# zulu_a7_3.net
KiCad netlist of a schematic drawn in Altium Designer
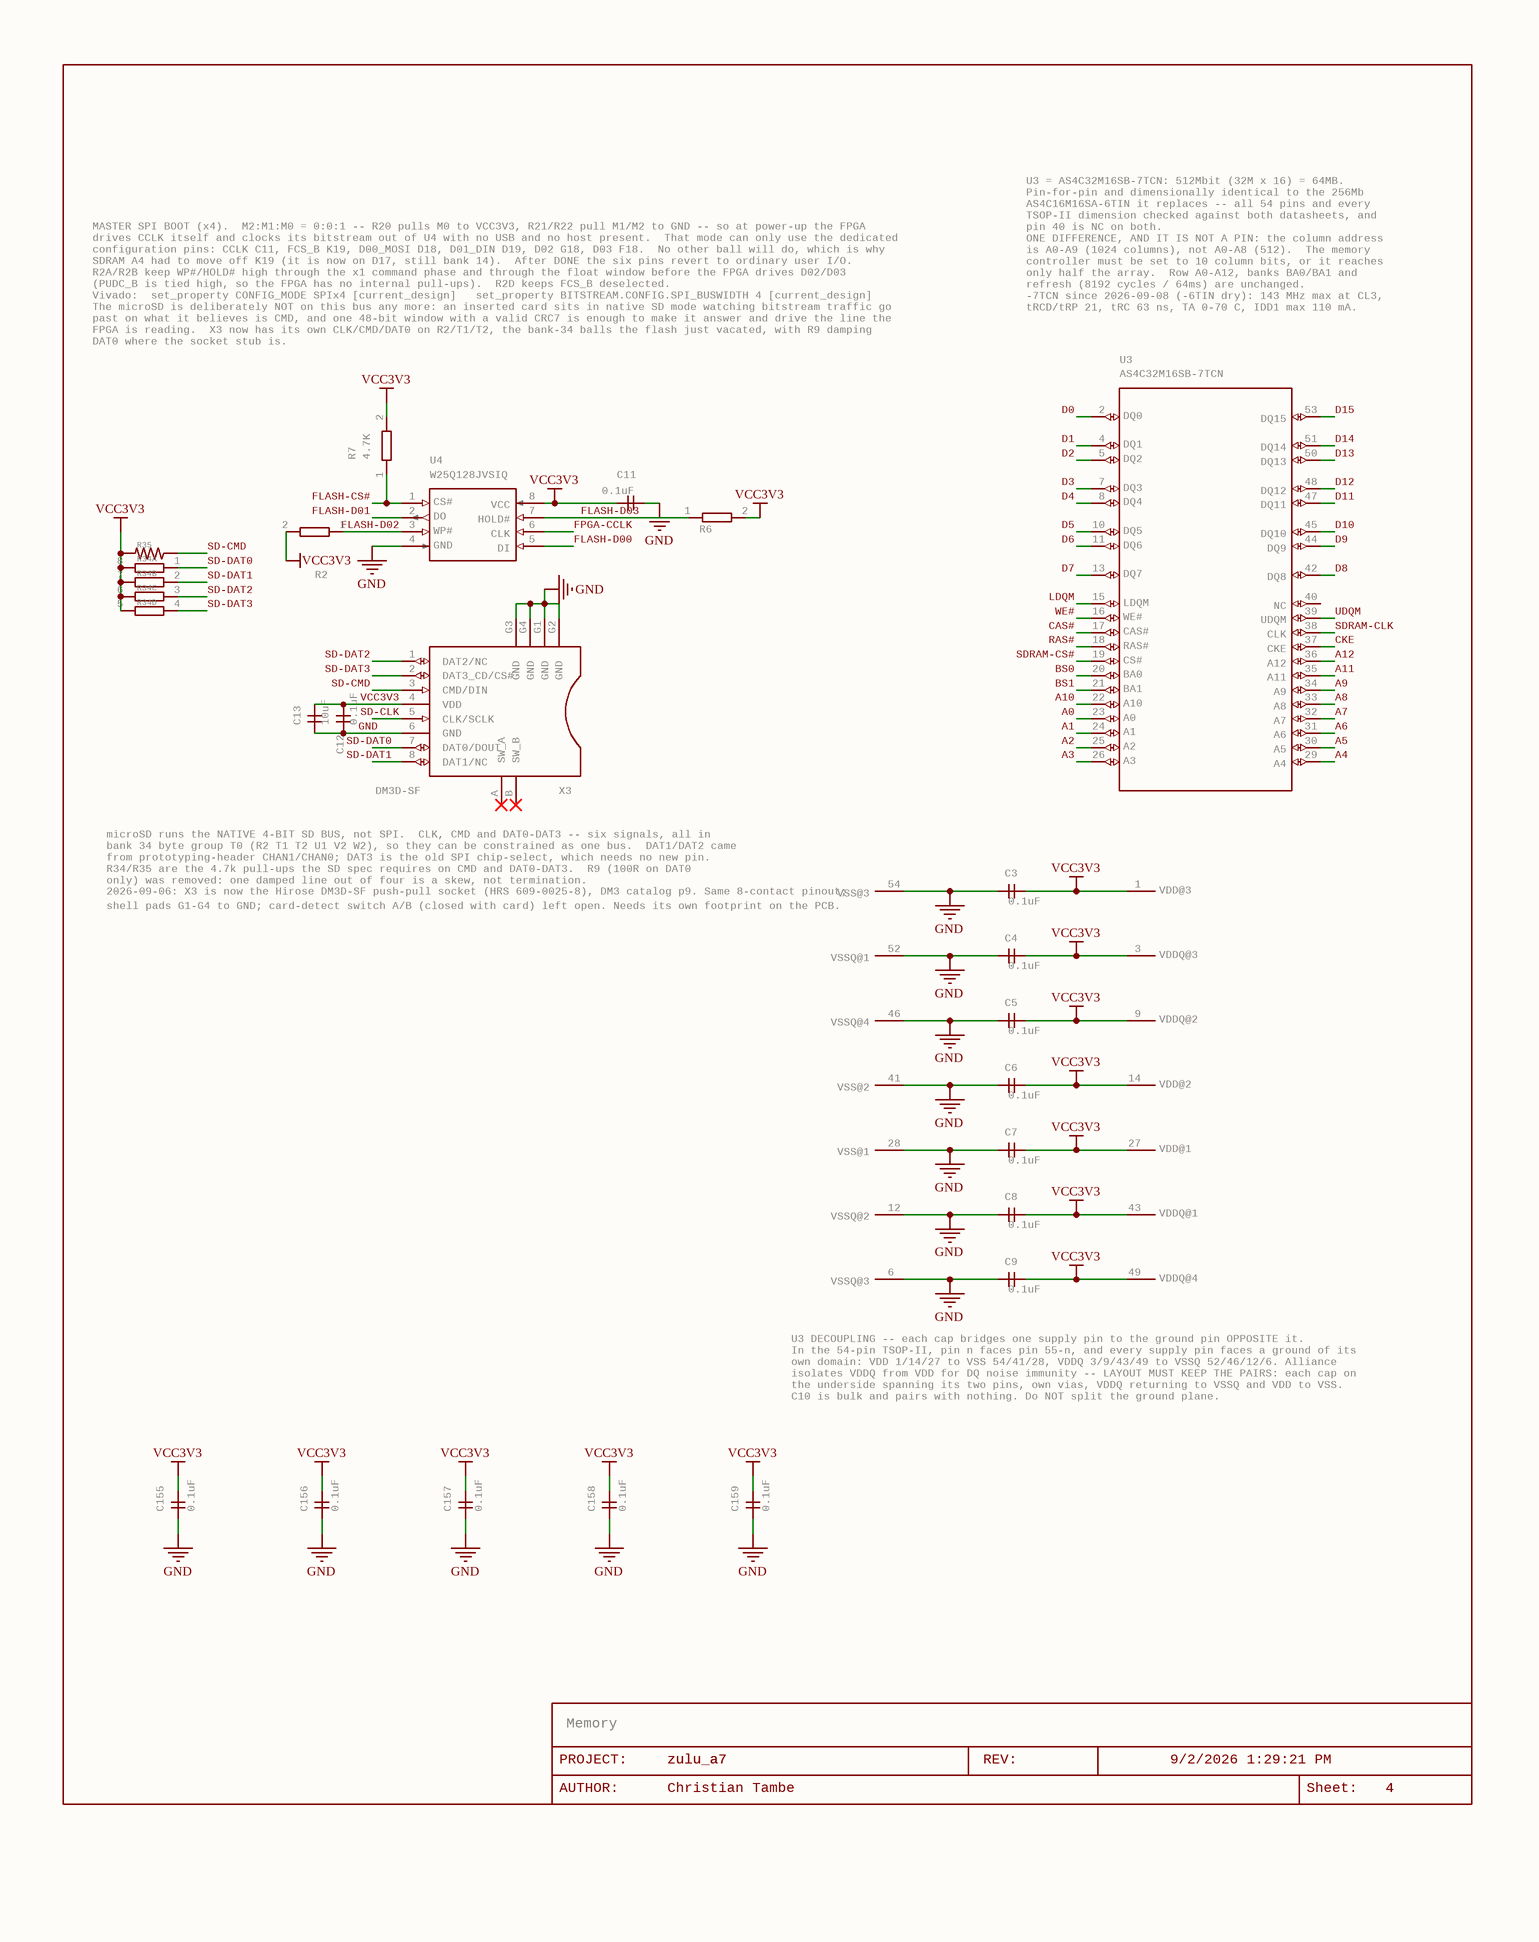
[diagram p0: zulu_a7_3.SchDoc]

(export (version "E")
  (design (tool "Eeschema 10.0.6"))
  (components
    (comp (ref "C3")
      (value "0.1uF")
      (footprint "C0402")
      (description "CAPACITOR, generic non-polarized, horizontal pins")
      (fields (field (name "MANF") "Murata"))
      (libsource (lib "") (part "C-GENERICC0402_3"))
    )
    (comp (ref "C4")
      (value "0.1uF")
      (footprint "C0402")
      (description "CAPACITOR, generic non-polarized, horizontal pins")
      (fields (field (name "MANF") "Murata"))
      (libsource (lib "") (part "C-GENERICC0402_6"))
    )
    (comp (ref "C5")
      (value "0.1uF")
      (footprint "C0402")
      (description "CAPACITOR, generic non-polarized, horizontal pins")
      (fields (field (name "MANF") "Murata"))
      (libsource (lib "") (part "C-GENERICC0402_5"))
    )
    (comp (ref "C6")
      (value "0.1uF")
      (footprint "C0402")
      (description "CAPACITOR, generic non-polarized, horizontal pins")
      (fields (field (name "MANF") "Murata"))
      (libsource (lib "rcl") (part "C-GENERICC0402"))
    )
    (comp (ref "C7")
      (value "0.1uF")
      (footprint "C0402")
      (description "CAPACITOR, generic non-polarized, horizontal pins")
      (fields (field (name "MANF") "Murata"))
      (libsource (lib "") (part "C-GENERICC0402_2"))
    )
    (comp (ref "C8")
      (value "0.1uF")
      (footprint "C0402")
      (description "CAPACITOR, generic non-polarized, horizontal pins")
      (fields (field (name "MANF") "Murata"))
      (libsource (lib "") (part "C-GENERICC0402_1"))
    )
    (comp (ref "C9")
      (value "0.1uF")
      (footprint "C0402")
      (description "CAPACITOR, generic non-polarized, horizontal pins")
      (fields (field (name "MANF") "Murata"))
      (libsource (lib "") (part "C-GENERICC0402_4"))
    )
    (comp (ref "C11")
      (value "0.1uF")
      (footprint "C0402")
      (description "CAPACITOR, generic non-polarized, horizontal pins")
      (fields (field (name "MANF") "Murata"))
      (libsource (lib "") (part "C-GENERICC0402_4"))
    )
    (comp (ref "C12")
      (value "0.1uF")
      (footprint "C0402")
      (description "CAPACITOR, generic non-polarized, horizontal pins")
      (fields (field (name "MANF") "Murata"))
      (libsource (lib "") (part "C-GENERICC0402_4"))
    )
    (comp (ref "C13")
      (value "10uF")
      (footprint "C0603")
      (description "CAPACITOR, generic non-polarized, horizontal pins")
      (fields (field (name "MANF") "Murata"))
      (libsource (lib "rcl") (part "C-GENERICC0603"))
    )
    (comp (ref "C155")
      (value "0.1uF")
      (footprint "C0201")
      (description "CAPACITOR, generic non-polarized, horizontal pins")
      (fields (field (name "MANF") "Murata"))
      (libsource (lib "rcl") (part "C-GENERICC0201"))
    )
    (comp (ref "C156")
      (value "0.1uF")
      (footprint "C0201")
      (description "CAPACITOR, generic non-polarized, horizontal pins")
      (fields (field (name "MANF") "Murata"))
      (libsource (lib "rcl") (part "C-GENERICC0201"))
    )
    (comp (ref "C157")
      (value "0.1uF")
      (footprint "C0201")
      (description "CAPACITOR, generic non-polarized, horizontal pins")
      (fields (field (name "MANF") "Murata"))
      (libsource (lib "rcl") (part "C-GENERICC0201"))
    )
    (comp (ref "C158")
      (value "0.1uF")
      (footprint "C0201")
      (description "CAPACITOR, generic non-polarized, horizontal pins")
      (fields (field (name "MANF") "Murata"))
      (libsource (lib "rcl") (part "C-GENERICC0201"))
    )
    (comp (ref "C159")
      (value "0.1uF")
      (footprint "C0201")
      (description "CAPACITOR, generic non-polarized, horizontal pins")
      (fields (field (name "MANF") "Murata"))
      (libsource (lib "rcl") (part "C-GENERICC0201"))
    )
    (comp (ref "FRAME7")
      (value "DOCFIELD")
      (description "DOCUMENT FIELD")
      (fields
        (field (name "LAST_DATE_TIME") "9/2/2026 1:29:21 PM")
        (field (name "SHEET") "Sheet:")
        (field (name "SHEET_1") "4")
        (field (name "REV") "REV:")
        (field (name "PROJECT") "PROJECT:")
        (field (name "DRAWING_NAME") "zulu_a7")
        (field (name "AUTHOR") "Christian Tambe")
        (field (name "DRAWING_NAME_1") "zulu_a7")
        (field (name "SHEET_2") "4")
        (field (name "LIBRARYNAME") "ctambe")
      )
      (libsource (lib "ctambe") (part "DOCFIELD"))
    )
    (comp (ref "R2")
      (value "4.7K")
      (footprint "R0201")
      (fields (field (name "MANF") "Yageo"))
      (libsource (lib "rcl") (part "R-WIDER0201"))
    )
    (comp (ref "R6")
      (value "4.7K")
      (footprint "R0201")
      (fields (field (name "MANF") "Yageo"))
      (libsource (lib "rcl") (part "R-WIDER0201"))
    )
    (comp (ref "R7")
      (value "4.7K")
      (footprint "R0201")
      (fields (field (name "MANF") "Yageo"))
      (libsource (lib "rcl") (part "R-WIDER0201"))
    )
    (comp (ref "R34")
      (value "4.7K")
      (footprint "742C083")
      (description "Resistor 4-pack   Package of four resistors.")
      (fields (field (name "MANF") "CTS") (field (name "LIBRARYNAME") "ctambe"))
      (libsource (lib "ctambe") (part "RES4742"))
    )
    (comp (ref "R35")
      (value "4.7K")
      (footprint "R0402")
      (description "RESISTOR, American symbol")
      (fields (field (name "MANF") "Yageo"))
      (libsource (lib "rcl") (part "R-US_R0402"))
    )
    (comp (ref "U3")
      (value "AS4C32M16SB-7TCN")
      (footprint "TSOPII-54")
      (fields
        (field (name "GATE") "VDD@2")
        (field (name "MANF") "Alliance Memory")
        (field (name "PART") "U3")
        (field (name "LIBRARYNAME") "ctambe")
      )
      (libsource (lib "ctambe") (part "SDRAM-X16-ALLIANCE-512M"))
    )
    (comp (ref "U4")
      (value "W25Q128JVSIQ")
      (footprint "SOIC-8_208MIL")
      (description "SPI Flash")
      (fields
        (field (name "GATE") "CS#")
        (field (name "MANF") "Winbond")
        (field (name "PART") "U4")
        (field (name "LIBRARYNAME") "ctambe")
      )
      (libsource (lib "ctambe") (part "SPI_FLASH-SOIC_150_208"))
    )
    (comp (ref "X3")
      (value "DM3D-SF")
      (footprint "DM3D-SF")
      (description "microSD socket, push-pull, Hirose DM3D-SF")
      (fields (field (name "MANF") "Hirose") (field (name "LIBRARYNAME") "ctambe"))
      (libsource (lib "ctambe") (part "MICROSD_CONDM3D-SF"))
    )
  )
  (nets
    (net (code "1") (name "/A0") (class "Default")
      (node (ref "U3") (pin "23") (pinfunction "P$1_23") (pintype "bidirectional"))
    )
    (net (code "2") (name "/A1") (class "Default")
      (node (ref "U3") (pin "24") (pinfunction "P$1_24") (pintype "bidirectional"))
    )
    (net (code "3") (name "/A2") (class "Default")
      (node (ref "U3") (pin "25") (pinfunction "P$1_25") (pintype "bidirectional"))
    )
    (net (code "4") (name "/A3") (class "Default")
      (node (ref "U3") (pin "26") (pinfunction "P$1_26") (pintype "bidirectional"))
    )
    (net (code "5") (name "/A4") (class "Default")
      (node (ref "U3") (pin "29") (pinfunction "P$1_29") (pintype "bidirectional"))
    )
    (net (code "6") (name "/A5") (class "Default")
      (node (ref "U3") (pin "30") (pinfunction "P$1_30") (pintype "bidirectional"))
    )
    (net (code "7") (name "/A6") (class "Default")
      (node (ref "U3") (pin "31") (pinfunction "P$1_31") (pintype "bidirectional"))
    )
    (net (code "8") (name "/A7") (class "Default")
      (node (ref "U3") (pin "32") (pinfunction "P$1_32") (pintype "bidirectional"))
    )
    (net (code "9") (name "/A8") (class "Default")
      (node (ref "U3") (pin "33") (pinfunction "P$1_33") (pintype "bidirectional"))
    )
    (net (code "10") (name "/A9") (class "Default")
      (node (ref "U3") (pin "34") (pinfunction "P$1_34") (pintype "bidirectional"))
    )
    (net (code "11") (name "/A10") (class "Default")
      (node (ref "U3") (pin "22") (pinfunction "P$1_22") (pintype "bidirectional"))
    )
    (net (code "12") (name "/A11") (class "Default")
      (node (ref "U3") (pin "35") (pinfunction "P$1_35") (pintype "bidirectional"))
    )
    (net (code "13") (name "/A12") (class "Default")
      (node (ref "U3") (pin "36") (pinfunction "P$1_36") (pintype "bidirectional"))
    )
    (net (code "14") (name "/BS0") (class "Default")
      (node (ref "U3") (pin "20") (pinfunction "P$1_20") (pintype "bidirectional"))
    )
    (net (code "15") (name "/BS1") (class "Default")
      (node (ref "U3") (pin "21") (pinfunction "P$1_21") (pintype "bidirectional"))
    )
    (net (code "16") (name "/CAS#") (class "Default")
      (node (ref "U3") (pin "17") (pinfunction "P$1_17") (pintype "bidirectional"))
    )
    (net (code "17") (name "/CKE") (class "Default")
      (node (ref "U3") (pin "37") (pinfunction "P$1_37") (pintype "bidirectional"))
    )
    (net (code "18") (name "/D0") (class "Default")
      (node (ref "U3") (pin "2") (pinfunction "P$1_2") (pintype "bidirectional"))
    )
    (net (code "19") (name "/D1") (class "Default")
      (node (ref "U3") (pin "4") (pinfunction "P$1_4") (pintype "bidirectional"))
    )
    (net (code "20") (name "/D2") (class "Default")
      (node (ref "U3") (pin "5") (pinfunction "P$1_5") (pintype "bidirectional"))
    )
    (net (code "21") (name "/D3") (class "Default")
      (node (ref "U3") (pin "7") (pinfunction "P$1_7") (pintype "bidirectional"))
    )
    (net (code "22") (name "/D4") (class "Default")
      (node (ref "U3") (pin "8") (pinfunction "P$1_8") (pintype "bidirectional"))
    )
    (net (code "23") (name "/D5") (class "Default")
      (node (ref "U3") (pin "10") (pinfunction "P$1_10") (pintype "bidirectional"))
    )
    (net (code "24") (name "/D6") (class "Default")
      (node (ref "U3") (pin "11") (pinfunction "P$1_11") (pintype "bidirectional"))
    )
    (net (code "25") (name "/D7") (class "Default")
      (node (ref "U3") (pin "13") (pinfunction "P$1_13") (pintype "bidirectional"))
    )
    (net (code "26") (name "/D8") (class "Default")
      (node (ref "U3") (pin "42") (pinfunction "P$1_42") (pintype "bidirectional"))
    )
    (net (code "27") (name "/D9") (class "Default")
      (node (ref "U3") (pin "44") (pinfunction "P$1_44") (pintype "bidirectional"))
    )
    (net (code "28") (name "/D10") (class "Default")
      (node (ref "U3") (pin "45") (pinfunction "P$1_45") (pintype "bidirectional"))
    )
    (net (code "29") (name "/D11") (class "Default")
      (node (ref "U3") (pin "47") (pinfunction "P$1_47") (pintype "bidirectional"))
    )
    (net (code "30") (name "/D12") (class "Default")
      (node (ref "U3") (pin "48") (pinfunction "P$1_48") (pintype "bidirectional"))
    )
    (net (code "31") (name "/D13") (class "Default")
      (node (ref "U3") (pin "50") (pinfunction "P$1_50") (pintype "bidirectional"))
    )
    (net (code "32") (name "/D14") (class "Default")
      (node (ref "U3") (pin "51") (pinfunction "P$1_51") (pintype "bidirectional"))
    )
    (net (code "33") (name "/D15") (class "Default")
      (node (ref "U3") (pin "53") (pinfunction "P$1_53") (pintype "bidirectional"))
    )
    (net (code "34") (name "/FLASH-CS#") (class "Default")
      (node (ref "R7") (pin "1") (pinfunction "1_1") (pintype "passive"))
      (node (ref "U4") (pin "1") (pinfunction "1_1") (pintype "input"))
    )
    (net (code "35") (name "/FLASH-D00") (class "Default")
      (node (ref "U4") (pin "5") (pinfunction "1_5") (pintype "input"))
    )
    (net (code "36") (name "/FLASH-D01") (class "Default")
      (node (ref "U4") (pin "2") (pinfunction "1_2") (pintype "output"))
    )
    (net (code "37") (name "/FLASH-D02") (class "Default")
      (node (ref "R2") (pin "1") (pinfunction "1_1") (pintype "passive"))
      (node (ref "U4") (pin "3") (pinfunction "1_3") (pintype "input"))
    )
    (net (code "38") (name "/FLASH-D03") (class "Default")
      (node (ref "R6") (pin "1") (pinfunction "1_1") (pintype "passive"))
      (node (ref "U4") (pin "7") (pinfunction "1_7") (pintype "input"))
    )
    (net (code "39") (name "/FPGA-CCLK") (class "Default")
      (node (ref "U4") (pin "6") (pinfunction "1_6") (pintype "input"))
    )
    (net (code "40") (name "/LDQM") (class "Default")
      (node (ref "U3") (pin "15") (pinfunction "P$1_15") (pintype "bidirectional"))
    )
    (net (code "41") (name "/RAS#") (class "Default")
      (node (ref "U3") (pin "18") (pinfunction "P$1_18") (pintype "bidirectional"))
    )
    (net (code "42") (name "/SD-CLK") (class "Default")
      (node (ref "X3") (pin "5") (pinfunction "CLK/SCLK_5") (pintype "input"))
    )
    (net (code "43") (name "/SD-CMD") (class "Default")
      (node (ref "R35") (pin "1") (pinfunction "1_1") (pintype "passive"))
      (node (ref "X3") (pin "3") (pinfunction "CMD/DIN_3") (pintype "input"))
    )
    (net (code "44") (name "/SD-DAT0") (class "Default")
      (node (ref "R34") (pin "1") (pinfunction "1_1") (pintype "passive"))
      (node (ref "X3") (pin "7") (pinfunction "DAT0/DOUT_7") (pintype "bidirectional"))
    )
    (net (code "45") (name "/SD-DAT1") (class "Default")
      (node (ref "R34") (pin "2") (pinfunction "1_2") (pintype "passive"))
      (node (ref "X3") (pin "8") (pinfunction "DAT1/NC_8") (pintype "bidirectional"))
    )
    (net (code "46") (name "/SD-DAT2") (class "Default")
      (node (ref "R34") (pin "3") (pinfunction "1_3") (pintype "passive"))
      (node (ref "X3") (pin "1") (pinfunction "DAT2/NC_1") (pintype "bidirectional"))
    )
    (net (code "47") (name "/SD-DAT3") (class "Default")
      (node (ref "R34") (pin "4") (pinfunction "1_4") (pintype "passive"))
      (node (ref "X3") (pin "2") (pinfunction "DAT3_CD/CS#_2") (pintype "bidirectional"))
    )
    (net (code "48") (name "/SDRAM-CLK") (class "Default")
      (node (ref "U3") (pin "38") (pinfunction "P$1_38") (pintype "bidirectional"))
    )
    (net (code "49") (name "/SDRAM-CS#") (class "Default")
      (node (ref "U3") (pin "19") (pinfunction "P$1_19") (pintype "bidirectional"))
    )
    (net (code "50") (name "/UDQM") (class "Default")
      (node (ref "U3") (pin "39") (pinfunction "P$1_39") (pintype "bidirectional"))
    )
    (net (code "51") (name "/WE#") (class "Default")
      (node (ref "U3") (pin "16") (pinfunction "P$1_16") (pintype "bidirectional"))
    )
    (net (code "52") (name "GND") (class "Default")
      (node (ref "C11") (pin "1") (pinfunction "1_1") (pintype "passive"))
      (node (ref "C12") (pin "1") (pinfunction "1_1") (pintype "passive"))
      (node (ref "C13") (pin "1") (pinfunction "1_1") (pintype "passive"))
      (node (ref "C155") (pin "1") (pinfunction "1_1") (pintype "passive"))
      (node (ref "C156") (pin "1") (pinfunction "1_1") (pintype "passive"))
      (node (ref "C157") (pin "1") (pinfunction "1_1") (pintype "passive"))
      (node (ref "C158") (pin "1") (pinfunction "1_1") (pintype "passive"))
      (node (ref "C159") (pin "1") (pinfunction "1_1") (pintype "passive"))
      (node (ref "C3") (pin "1") (pinfunction "1_1") (pintype "passive"))
      (node (ref "C4") (pin "1") (pinfunction "1_1") (pintype "passive"))
      (node (ref "C5") (pin "1") (pinfunction "1_1") (pintype "passive"))
      (node (ref "C6") (pin "1") (pinfunction "1_1") (pintype "passive"))
      (node (ref "C7") (pin "1") (pinfunction "1_1") (pintype "passive"))
      (node (ref "C8") (pin "1") (pinfunction "1_1") (pintype "passive"))
      (node (ref "C9") (pin "1") (pinfunction "1_1") (pintype "passive"))
      (node (ref "U3") (pin "12") (pinfunction "P$1_12") (pintype "power_in"))
      (node (ref "U3") (pin "28") (pinfunction "P$1_28") (pintype "power_in"))
      (node (ref "U3") (pin "41") (pinfunction "P$1_41") (pintype "power_in"))
      (node (ref "U3") (pin "46") (pinfunction "P$1_46") (pintype "power_in"))
      (node (ref "U3") (pin "52") (pinfunction "P$1_52") (pintype "power_in"))
      (node (ref "U3") (pin "54") (pinfunction "P$1_54") (pintype "power_in"))
      (node (ref "U3") (pin "6") (pinfunction "P$1_6") (pintype "power_in"))
      (node (ref "U4") (pin "4") (pinfunction "1_4") (pintype "input"))
      (node (ref "X3") (pin "6") (pinfunction "GND_6") (pintype "passive"))
      (node (ref "X3") (pin "G1") (pinfunction "GND_G1") (pintype "passive"))
      (node (ref "X3") (pin "G2") (pinfunction "GND_G2") (pintype "passive"))
      (node (ref "X3") (pin "G3") (pinfunction "GND_G3") (pintype "passive"))
      (node (ref "X3") (pin "G4") (pinfunction "GND_G4") (pintype "passive"))
    )
    (net (code "53") (name "VCC3V3") (class "Default")
      (node (ref "C11") (pin "2") (pinfunction "2_2") (pintype "passive"))
      (node (ref "C12") (pin "2") (pinfunction "2_2") (pintype "passive"))
      (node (ref "C13") (pin "2") (pinfunction "2_2") (pintype "passive"))
      (node (ref "C155") (pin "2") (pinfunction "2_2") (pintype "passive"))
      (node (ref "C156") (pin "2") (pinfunction "2_2") (pintype "passive"))
      (node (ref "C157") (pin "2") (pinfunction "2_2") (pintype "passive"))
      (node (ref "C158") (pin "2") (pinfunction "2_2") (pintype "passive"))
      (node (ref "C159") (pin "2") (pinfunction "2_2") (pintype "passive"))
      (node (ref "C3") (pin "2") (pinfunction "2_2") (pintype "passive"))
      (node (ref "C4") (pin "2") (pinfunction "2_2") (pintype "passive"))
      (node (ref "C5") (pin "2") (pinfunction "2_2") (pintype "passive"))
      (node (ref "C6") (pin "2") (pinfunction "2_2") (pintype "passive"))
      (node (ref "C7") (pin "2") (pinfunction "2_2") (pintype "passive"))
      (node (ref "C8") (pin "2") (pinfunction "2_2") (pintype "passive"))
      (node (ref "C9") (pin "2") (pinfunction "2_2") (pintype "passive"))
      (node (ref "R2") (pin "2") (pinfunction "2_2") (pintype "passive"))
      (node (ref "R34") (pin "5") (pinfunction "2_5") (pintype "passive"))
      (node (ref "R34") (pin "6") (pinfunction "2_6") (pintype "passive"))
      (node (ref "R34") (pin "7") (pinfunction "2_7") (pintype "passive"))
      (node (ref "R34") (pin "8") (pinfunction "2_8") (pintype "passive"))
      (node (ref "R35") (pin "2") (pinfunction "2_2") (pintype "passive"))
      (node (ref "R6") (pin "2") (pinfunction "2_2") (pintype "passive"))
      (node (ref "R7") (pin "2") (pinfunction "2_2") (pintype "passive"))
      (node (ref "U3") (pin "1") (pinfunction "P$1_1") (pintype "power_in"))
      (node (ref "U3") (pin "14") (pinfunction "P$1_14") (pintype "power_in"))
      (node (ref "U3") (pin "27") (pinfunction "P$1_27") (pintype "power_in"))
      (node (ref "U3") (pin "3") (pinfunction "P$1_3") (pintype "power_in"))
      (node (ref "U3") (pin "43") (pinfunction "P$1_43") (pintype "power_in"))
      (node (ref "U3") (pin "49") (pinfunction "P$1_49") (pintype "power_in"))
      (node (ref "U3") (pin "9") (pinfunction "P$1_9") (pintype "power_in"))
      (node (ref "U4") (pin "8") (pinfunction "1_8") (pintype "input"))
      (node (ref "X3") (pin "4") (pinfunction "VDD_4") (pintype "passive"))
    )
    (net (code "54") (name "unconnected-(U3AO-P$1-Pad40)") (class "Default")
      (node (ref "U3") (pin "40") (pinfunction "P$1_40") (pintype "bidirectional"))
    )
    (net (code "55") (name "unconnected-(X3-SW_A-PadA)") (class "Default")
      (node (ref "X3") (pin "A") (pinfunction "SW_A_A") (pintype "passive+no_connect"))
    )
    (net (code "56") (name "unconnected-(X3-SW_B-PadB)") (class "Default")
      (node (ref "X3") (pin "B") (pinfunction "SW_B_B") (pintype "passive+no_connect"))
    )
  )
)
